# 2016_CARTE_PUISSANCE.net
KiCad netlist of a schematic drawn in Altium Designer
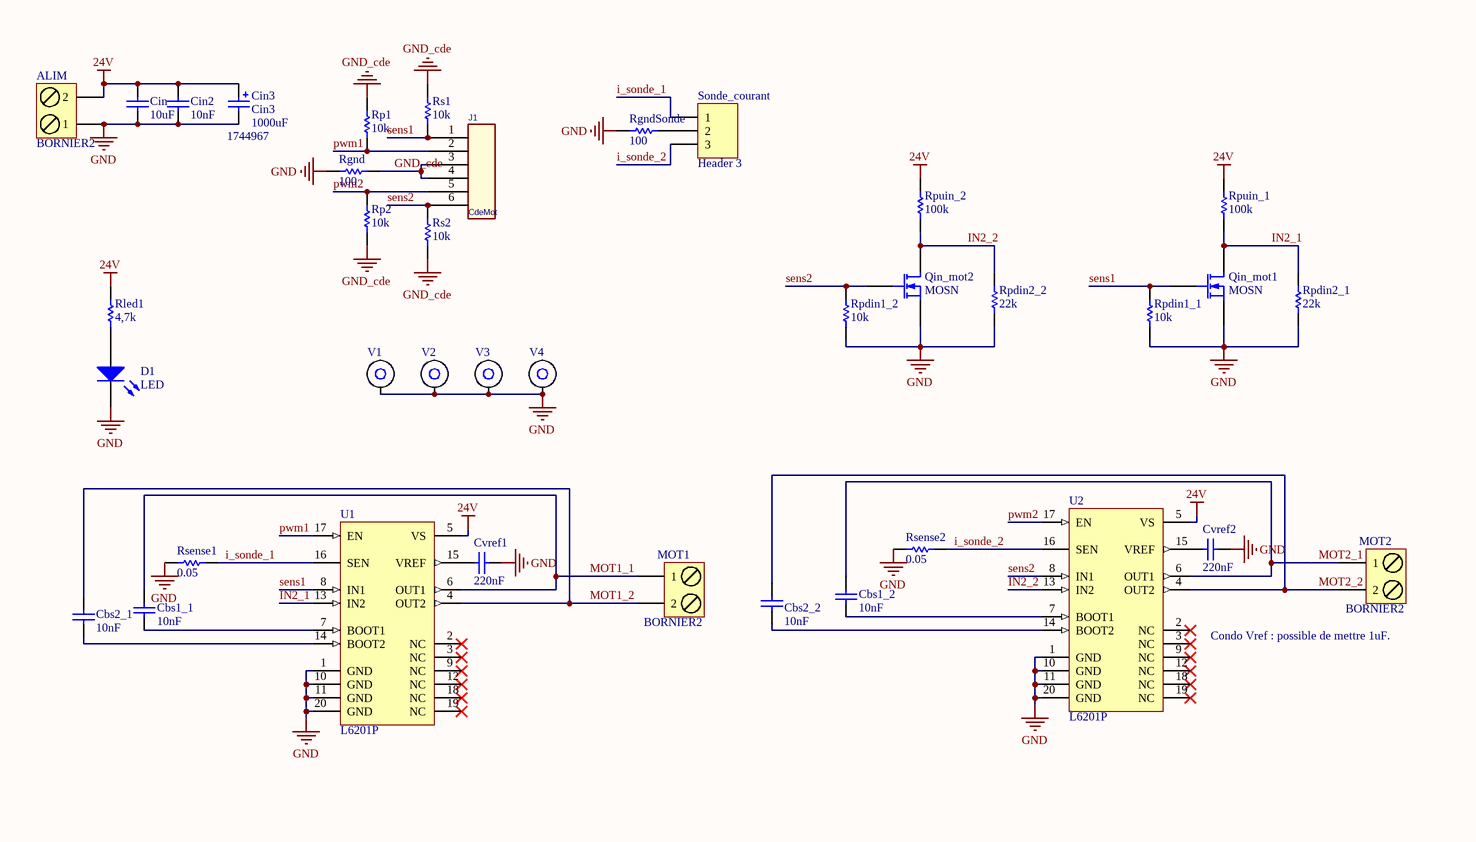
[diagram p0: 2016_CARTE_PUISSANCE.SchDoc, left]
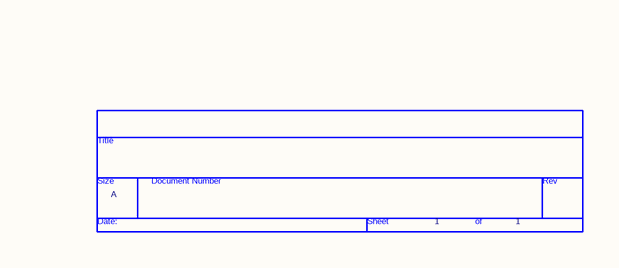
[diagram p1: 2016_CARTE_PUISSANCE.SchDoc, right]

(export (version "E")
  (design (tool "Eeschema 10.0.6"))
  (components
    (comp (ref "*")
      (value "TitleBlock0")
      (fields (field (name "PAGE COUNT") "1") (field (name "PAGE NUMBER") "1") (field (name "PAGE SIZE") "A"))
      (libsource (lib "*") (part "TitleBlock0"))
    )
    (comp (ref "ALIM")
      (value "BORNIER2")
      (footprint "BORNIER2")
      (description "Terminal blocks, 2 pins, pitch=5mm")
      (libsource (lib "Robot2010") (part "BORNIER2"))
    )
    (comp (ref "Cbs1_1")
      (value "10nF")
      (footprint "C0805_N")
      (description "Capacitor")
      (fields (field (name "PUBLISHER") "Altium Limited"))
      (libsource (lib "DG_Condensateur") (part "Capacitor"))
    )
    (comp (ref "Cbs1_2")
      (value "10nF")
      (footprint "C0805_N")
      (description "Capacitor")
      (fields (field (name "PUBLISHER") "Altium Limited"))
      (libsource (lib "DG_Condensateur") (part "Capacitor"))
    )
    (comp (ref "Cbs2_1")
      (value "10nF")
      (footprint "C0805_N")
      (description "Capacitor")
      (fields (field (name "PUBLISHER") "Altium Limited"))
      (libsource (lib "DG_Condensateur") (part "Capacitor"))
    )
    (comp (ref "Cbs2_2")
      (value "10nF")
      (footprint "C0805_N")
      (description "Capacitor")
      (fields (field (name "PUBLISHER") "Altium Limited"))
      (libsource (lib "DG_Condensateur") (part "Capacitor"))
    )
    (comp (ref "Cin")
      (value "10uF")
      (footprint "C1206_N")
      (description "Capacitor")
      (fields (field (name "PUBLISHER") "Altium Limited"))
      (libsource (lib "DG_Condensateur") (part "Capacitor"))
    )
    (comp (ref "Cin2")
      (value "10nF")
      (footprint "C0805_N")
      (description "Capacitor")
      (fields (field (name "PUBLISHER") "Altium Limited"))
      (libsource (lib "DG_Condensateur") (part "Capacitor"))
    )
    (comp (ref "Cin3")
      (value "Cin3")
      (footprint "COND_POL_RAD_5.08B")
      (description "Polarized Capacitor")
      (fields
        (field (name "ALTIUM_VALUE") "1000uF")
        (field (name "FAR") "1744967")
        (field (name "PUBLISHER") "Altium Limited")
      )
      (libsource (lib "Robot2010") (part "CONDENSATEUR_POLARISE"))
    )
    (comp (ref "Cvref1")
      (value "220nF")
      (footprint "C0805_N")
      (description "Capacitor")
      (fields (field (name "PUBLISHER") "Altium Limited"))
      (libsource (lib "DG_Condensateur") (part "Capacitor"))
    )
    (comp (ref "Cvref2")
      (value "220nF")
      (footprint "C0805_N")
      (description "Capacitor")
      (fields (field (name "PUBLISHER") "Altium Limited"))
      (libsource (lib "DG_Condensateur") (part "Capacitor"))
    )
    (comp (ref "D1")
      (value "LED")
      (footprint "LED_3mm")
      (description "Typical LED")
      (fields (field (name "PUBLISHER") "Altium Limited"))
      (libsource (lib "DG_LED") (part "LED"))
    )
    (comp (ref "J1") (value "CdeMot") (footprint "RJ11_6/6") (libsource (lib "*") (part "CONNECTEUR_RJ12")))
    (comp (ref "MOT1")
      (value "BORNIER2")
      (footprint "BORNIER2")
      (description "Terminal blocks, 2 pins, pitch=5mm")
      (libsource (lib "Connecteur") (part "BORNIER2"))
    )
    (comp (ref "MOT2")
      (value "BORNIER2")
      (footprint "BORNIER2")
      (description "Terminal blocks, 2 pins, pitch=5mm")
      (libsource (lib "Connecteur") (part "BORNIER2"))
    )
    (comp (ref "Qin_mot1")
      (value "MOSN")
      (footprint "SOT23-3N")
      (description "N-Channel MOSFET")
      (fields (field (name "PUBLISHER") "Altium Limited"))
      (libsource (lib "_ROBOT") (part "Transistor MOSFET-N"))
    )
    (comp (ref "Qin_mot2")
      (value "MOSN")
      (footprint "SOT23-3N")
      (description "N-Channel MOSFET")
      (fields (field (name "PUBLISHER") "Altium Limited"))
      (libsource (lib "_ROBOT") (part "Transistor MOSFET-N"))
    )
    (comp (ref "Rgnd")
      (value "100")
      (footprint "R1206_N")
      (description "Resistor")
      (fields (field (name "PUBLISHER") "Altium Limited"))
      (libsource (lib "DG_Resistance") (part "Resistor"))
    )
    (comp (ref "RgndSonde")
      (value "100")
      (footprint "R1206_N")
      (description "Resistor")
      (fields (field (name "PUBLISHER") "Altium Limited"))
      (libsource (lib "DG_Resistance") (part "Resistor"))
    )
    (comp (ref "Rled1")
      (value "4,7k")
      (footprint "R1206_N")
      (description "Resistor")
      (fields (field (name "PUBLISHER") "Altium Limited"))
      (libsource (lib "DG_Resistance") (part "Resistor"))
    )
    (comp (ref "Rp1")
      (value "10k")
      (footprint "R1206_N")
      (description "Resistor")
      (fields (field (name "PUBLISHER") "Altium Limited"))
      (libsource (lib "DG_Resistance") (part "Resistor"))
    )
    (comp (ref "Rp2")
      (value "10k")
      (footprint "R1206_N")
      (description "Resistor")
      (fields (field (name "PUBLISHER") "Altium Limited"))
      (libsource (lib "DG_Resistance") (part "Resistor"))
    )
    (comp (ref "Rpdin1_1")
      (value "10k")
      (footprint "R1206_N")
      (description "Resistor")
      (fields (field (name "PUBLISHER") "Altium Limited"))
      (libsource (lib "DG_Resistance") (part "Resistor"))
    )
    (comp (ref "Rpdin1_2")
      (value "10k")
      (footprint "R1206_N")
      (description "Resistor")
      (fields (field (name "PUBLISHER") "Altium Limited"))
      (libsource (lib "DG_Resistance") (part "Resistor"))
    )
    (comp (ref "Rpdin2_1")
      (value "22k")
      (footprint "R1206_N")
      (description "Resistor")
      (fields (field (name "PUBLISHER") "Altium Limited"))
      (libsource (lib "DG_Resistance") (part "Resistor"))
    )
    (comp (ref "Rpdin2_2")
      (value "22k")
      (footprint "R1206_N")
      (description "Resistor")
      (fields (field (name "PUBLISHER") "Altium Limited"))
      (libsource (lib "DG_Resistance") (part "Resistor"))
    )
    (comp (ref "Rpuin_1")
      (value "100k")
      (footprint "R1206_N")
      (description "Resistor")
      (fields (field (name "PUBLISHER") "Altium Limited"))
      (libsource (lib "DG_Resistance") (part "Resistor"))
    )
    (comp (ref "Rpuin_2")
      (value "100k")
      (footprint "R1206_N")
      (description "Resistor")
      (fields (field (name "PUBLISHER") "Altium Limited"))
      (libsource (lib "DG_Resistance") (part "Resistor"))
    )
    (comp (ref "Rs1")
      (value "10k")
      (footprint "R1206_N")
      (description "Resistor")
      (fields (field (name "PUBLISHER") "Altium Limited"))
      (libsource (lib "DG_Resistance") (part "Resistor"))
    )
    (comp (ref "Rs2")
      (value "10k")
      (footprint "R1206_N")
      (description "Resistor")
      (fields (field (name "PUBLISHER") "Altium Limited"))
      (libsource (lib "DG_Resistance") (part "Resistor"))
    )
    (comp (ref "Rsense1")
      (value "0.05")
      (footprint "R2512_N")
      (description "Resistor")
      (fields (field (name "PUBLISHER") "Altium Limited"))
      (libsource (lib "DG_Resistance") (part "Resistor"))
    )
    (comp (ref "Rsense2")
      (value "0.05")
      (footprint "R2512_N")
      (description "Resistor")
      (fields (field (name "PUBLISHER") "Altium Limited"))
      (libsource (lib "DG_Resistance") (part "Resistor"))
    )
    (comp (ref "Sonde_courant")
      (value "Header 3")
      (footprint "HDR1X3")
      (description "Header, 3-Pin")
      (fields (field (name "PUBLISHER") "Altium Limited"))
      (libsource (lib "DG_Connecteur") (part "Header 3"))
    )
    (comp (ref "U1")
      (value "L6201P")
      (footprint "PowerSO20_N")
      (description "DMOS Full Bridge Driver")
      (fields (field (name "PUBLISHER") "Altium Limited"))
      (libsource (lib "ST Interface DC Motor Controller") (part "L6201P"))
    )
    (comp (ref "U2")
      (value "L6201P")
      (footprint "PowerSO20_N")
      (description "DMOS Full Bridge Driver")
      (fields (field (name "PUBLISHER") "Altium Limited"))
      (libsource (lib "ST Interface DC Motor Controller") (part "L6201P"))
    )
    (comp (ref "V1")
      (value "Entretoise WURTH CMS")
      (footprint "ENTRETOISE_CMS")
      (description "Entretoise Wurth")
      (fields (field (name "PUBLISHER") "Damien Guitton"))
      (libsource (lib "_ROBOT") (part "Entretoise WURTH CMS"))
    )
    (comp (ref "V2")
      (value "Entretoise WURTH CMS")
      (footprint "ENTRETOISE_CMS")
      (description "Entretoise Wurth")
      (fields (field (name "PUBLISHER") "Damien Guitton"))
      (libsource (lib "_ROBOT") (part "Entretoise WURTH CMS"))
    )
    (comp (ref "V3")
      (value "Entretoise WURTH CMS")
      (footprint "ENTRETOISE_CMS")
      (description "Entretoise Wurth")
      (fields (field (name "PUBLISHER") "Damien Guitton"))
      (libsource (lib "_ROBOT") (part "Entretoise WURTH CMS"))
    )
    (comp (ref "V4")
      (value "Entretoise WURTH CMS")
      (footprint "ENTRETOISE_CMS")
      (description "Entretoise Wurth")
      (fields (field (name "PUBLISHER") "Damien Guitton"))
      (libsource (lib "_ROBOT") (part "Entretoise WURTH CMS"))
    )
  )
  (nets
    (net (code "1") (name "/IN2_1") (class "Default")
      (node (ref "Qin_mot1") (pin "3") (pinfunction "D_3") (pintype "passive"))
      (node (ref "Rpdin2_1") (pin "2") (pinfunction "2_2") (pintype "passive"))
      (node (ref "Rpuin_1") (pin "1") (pinfunction "1_1") (pintype "passive"))
      (node (ref "U1") (pin "13") (pinfunction "IN2_13") (pintype "input"))
    )
    (net (code "2") (name "/IN2_2") (class "Default")
      (node (ref "Qin_mot2") (pin "3") (pinfunction "D_3") (pintype "passive"))
      (node (ref "Rpdin2_2") (pin "2") (pinfunction "2_2") (pintype "passive"))
      (node (ref "Rpuin_2") (pin "1") (pinfunction "1_1") (pintype "passive"))
      (node (ref "U2") (pin "13") (pinfunction "IN2_13") (pintype "input"))
    )
    (net (code "3") (name "/MOT1_1") (class "Default")
      (node (ref "Cbs1_1") (pin "2") (pinfunction "2_2") (pintype "passive"))
      (node (ref "MOT1") (pin "1") (pinfunction "1_1") (pintype "passive"))
      (node (ref "U1") (pin "6") (pinfunction "OUT1_6") (pintype "output"))
    )
    (net (code "4") (name "/MOT1_2") (class "Default")
      (node (ref "Cbs2_1") (pin "2") (pinfunction "2_2") (pintype "passive"))
      (node (ref "MOT1") (pin "2") (pinfunction "2_2") (pintype "passive"))
      (node (ref "U1") (pin "4") (pinfunction "OUT2_4") (pintype "output"))
    )
    (net (code "5") (name "/MOT2_1") (class "Default")
      (node (ref "Cbs1_2") (pin "2") (pinfunction "2_2") (pintype "passive"))
      (node (ref "MOT2") (pin "1") (pinfunction "1_1") (pintype "passive"))
      (node (ref "U2") (pin "6") (pinfunction "OUT1_6") (pintype "output"))
    )
    (net (code "6") (name "/MOT2_2") (class "Default")
      (node (ref "Cbs2_2") (pin "2") (pinfunction "2_2") (pintype "passive"))
      (node (ref "MOT2") (pin "2") (pinfunction "2_2") (pintype "passive"))
      (node (ref "U2") (pin "4") (pinfunction "OUT2_4") (pintype "output"))
    )
    (net (code "7") (name "/i_sonde_1") (class "Default")
      (node (ref "Rsense1") (pin "2") (pinfunction "2_2") (pintype "passive"))
      (node (ref "Sonde_courant") (pin "1") (pinfunction "1_1") (pintype "passive"))
      (node (ref "U1") (pin "16") (pinfunction "SEN_16") (pintype "passive"))
    )
    (net (code "8") (name "/i_sonde_2") (class "Default")
      (node (ref "Rsense2") (pin "2") (pinfunction "2_2") (pintype "passive"))
      (node (ref "Sonde_courant") (pin "3") (pinfunction "3_3") (pintype "passive"))
      (node (ref "U2") (pin "16") (pinfunction "SEN_16") (pintype "passive"))
    )
    (net (code "9") (name "/pwm1") (class "Default")
      (node (ref "J1") (pin "2") (pinfunction "2_2") (pintype "passive"))
      (node (ref "Rp1") (pin "1") (pinfunction "1_1") (pintype "passive"))
      (node (ref "U1") (pin "17") (pinfunction "EN_17") (pintype "input"))
    )
    (net (code "10") (name "/pwm2") (class "Default")
      (node (ref "J1") (pin "5") (pinfunction "5_5") (pintype "passive"))
      (node (ref "Rp2") (pin "2") (pinfunction "2_2") (pintype "passive"))
      (node (ref "U2") (pin "17") (pinfunction "EN_17") (pintype "input"))
    )
    (net (code "11") (name "/sens1") (class "Default")
      (node (ref "J1") (pin "1") (pinfunction "1_1") (pintype "passive"))
      (node (ref "Qin_mot1") (pin "1") (pinfunction "G_1") (pintype "passive"))
      (node (ref "Rpdin1_1") (pin "1") (pinfunction "1_1") (pintype "passive"))
      (node (ref "Rs1") (pin "1") (pinfunction "1_1") (pintype "passive"))
      (node (ref "U1") (pin "8") (pinfunction "IN1_8") (pintype "input"))
    )
    (net (code "12") (name "/sens2") (class "Default")
      (node (ref "J1") (pin "6") (pinfunction "6_6") (pintype "passive"))
      (node (ref "Qin_mot2") (pin "1") (pinfunction "G_1") (pintype "passive"))
      (node (ref "Rpdin1_2") (pin "1") (pinfunction "1_1") (pintype "passive"))
      (node (ref "Rs2") (pin "2") (pinfunction "2_2") (pintype "passive"))
      (node (ref "U2") (pin "8") (pinfunction "IN1_8") (pintype "input"))
    )
    (net (code "13") (name "24V") (class "Default")
      (node (ref "ALIM") (pin "2") (pinfunction "2_2") (pintype "passive"))
      (node (ref "Cin") (pin "2") (pinfunction "2_2") (pintype "passive"))
      (node (ref "Cin2") (pin "2") (pinfunction "2_2") (pintype "passive"))
      (node (ref "Cin3") (pin "1") (pinfunction "1_1") (pintype "passive"))
      (node (ref "Rled1") (pin "2") (pinfunction "2_2") (pintype "passive"))
      (node (ref "Rpuin_1") (pin "2") (pinfunction "2_2") (pintype "passive"))
      (node (ref "Rpuin_2") (pin "2") (pinfunction "2_2") (pintype "passive"))
      (node (ref "U1") (pin "5") (pinfunction "VS_5") (pintype "power_in"))
      (node (ref "U2") (pin "5") (pinfunction "VS_5") (pintype "power_in"))
    )
    (net (code "14") (name "GND") (class "Default")
      (node (ref "ALIM") (pin "1") (pinfunction "1_1") (pintype "passive"))
      (node (ref "Cin") (pin "1") (pinfunction "1_1") (pintype "passive"))
      (node (ref "Cin2") (pin "1") (pinfunction "1_1") (pintype "passive"))
      (node (ref "Cin3") (pin "2") (pinfunction "2_2") (pintype "passive"))
      (node (ref "Cvref1") (pin "1") (pinfunction "1_1") (pintype "passive"))
      (node (ref "Cvref2") (pin "1") (pinfunction "1_1") (pintype "passive"))
      (node (ref "D1") (pin "2") (pinfunction "2_2") (pintype "passive"))
      (node (ref "Qin_mot1") (pin "2") (pinfunction "S_2") (pintype "passive"))
      (node (ref "Qin_mot2") (pin "2") (pinfunction "S_2") (pintype "passive"))
      (node (ref "Rgnd") (pin "2") (pinfunction "2_2") (pintype "passive"))
      (node (ref "RgndSonde") (pin "2") (pinfunction "2_2") (pintype "passive"))
      (node (ref "Rpdin1_1") (pin "2") (pinfunction "2_2") (pintype "passive"))
      (node (ref "Rpdin1_2") (pin "2") (pinfunction "2_2") (pintype "passive"))
      (node (ref "Rpdin2_1") (pin "1") (pinfunction "1_1") (pintype "passive"))
      (node (ref "Rpdin2_2") (pin "1") (pinfunction "1_1") (pintype "passive"))
      (node (ref "Rsense1") (pin "1") (pinfunction "1_1") (pintype "passive"))
      (node (ref "Rsense2") (pin "1") (pinfunction "1_1") (pintype "passive"))
      (node (ref "U1") (pin "1") (pinfunction "GND_1") (pintype "power_in"))
      (node (ref "U1") (pin "10") (pinfunction "GND_10") (pintype "power_in"))
      (node (ref "U1") (pin "11") (pinfunction "GND_11") (pintype "power_in"))
      (node (ref "U1") (pin "20") (pinfunction "GND_20") (pintype "power_in"))
      (node (ref "U2") (pin "1") (pinfunction "GND_1") (pintype "power_in"))
      (node (ref "U2") (pin "10") (pinfunction "GND_10") (pintype "power_in"))
      (node (ref "U2") (pin "11") (pinfunction "GND_11") (pintype "power_in"))
      (node (ref "U2") (pin "20") (pinfunction "GND_20") (pintype "power_in"))
      (node (ref "V1") (pin "1") (pinfunction "1_1") (pintype "passive"))
      (node (ref "V2") (pin "1") (pinfunction "1_1") (pintype "passive"))
      (node (ref "V3") (pin "1") (pinfunction "1_1") (pintype "passive"))
      (node (ref "V4") (pin "1") (pinfunction "1_1") (pintype "passive"))
    )
    (net (code "15") (name "GND_cde") (class "Default")
      (node (ref "J1") (pin "3") (pinfunction "3_3") (pintype "passive"))
      (node (ref "J1") (pin "4") (pinfunction "4_4") (pintype "passive"))
      (node (ref "Rgnd") (pin "1") (pinfunction "1_1") (pintype "passive"))
      (node (ref "Rp1") (pin "2") (pinfunction "2_2") (pintype "passive"))
      (node (ref "Rp2") (pin "1") (pinfunction "1_1") (pintype "passive"))
      (node (ref "Rs1") (pin "2") (pinfunction "2_2") (pintype "passive"))
      (node (ref "Rs2") (pin "1") (pinfunction "1_1") (pintype "passive"))
    )
    (net (code "16") (name "Net-(D1-Pad1)") (class "Default")
      (node (ref "D1") (pin "1") (pinfunction "1_1") (pintype "passive"))
      (node (ref "Rled1") (pin "1") (pinfunction "1_1") (pintype "passive"))
    )
    (net (code "17") (name "Net-(RgndSonde-Pad1)") (class "Default")
      (node (ref "RgndSonde") (pin "1") (pinfunction "1_1") (pintype "passive"))
      (node (ref "Sonde_courant") (pin "2") (pinfunction "2_2") (pintype "passive"))
    )
    (net (code "18") (name "Net-(U1-BOOT1)") (class "Default")
      (node (ref "Cbs1_1") (pin "1") (pinfunction "1_1") (pintype "passive"))
      (node (ref "U1") (pin "7") (pinfunction "BOOT1_7") (pintype "input"))
    )
    (net (code "19") (name "Net-(U1-BOOT2)") (class "Default")
      (node (ref "Cbs2_1") (pin "1") (pinfunction "1_1") (pintype "passive"))
      (node (ref "U1") (pin "14") (pinfunction "BOOT2_14") (pintype "input"))
    )
    (net (code "20") (name "Net-(U1-VREF)") (class "Default")
      (node (ref "Cvref1") (pin "2") (pinfunction "2_2") (pintype "passive"))
      (node (ref "U1") (pin "15") (pinfunction "VREF_15") (pintype "output"))
    )
    (net (code "21") (name "Net-(U2-BOOT1)") (class "Default")
      (node (ref "Cbs1_2") (pin "1") (pinfunction "1_1") (pintype "passive"))
      (node (ref "U2") (pin "7") (pinfunction "BOOT1_7") (pintype "input"))
    )
    (net (code "22") (name "Net-(U2-BOOT2)") (class "Default")
      (node (ref "Cbs2_2") (pin "1") (pinfunction "1_1") (pintype "passive"))
      (node (ref "U2") (pin "14") (pinfunction "BOOT2_14") (pintype "input"))
    )
    (net (code "23") (name "Net-(U2-VREF)") (class "Default")
      (node (ref "Cvref2") (pin "2") (pinfunction "2_2") (pintype "passive"))
      (node (ref "U2") (pin "15") (pinfunction "VREF_15") (pintype "output"))
    )
    (net (code "24") (name "unconnected-(U1-NC-Pad2)") (class "Default")
      (node (ref "U1") (pin "2") (pinfunction "NC_2") (pintype "passive+no_connect"))
    )
    (net (code "25") (name "unconnected-(U1-NC-Pad3)") (class "Default")
      (node (ref "U1") (pin "3") (pinfunction "NC_3") (pintype "passive+no_connect"))
    )
    (net (code "26") (name "unconnected-(U1-NC-Pad9)") (class "Default")
      (node (ref "U1") (pin "9") (pinfunction "NC_9") (pintype "passive+no_connect"))
    )
    (net (code "27") (name "unconnected-(U1-NC-Pad12)") (class "Default")
      (node (ref "U1") (pin "12") (pinfunction "NC_12") (pintype "passive+no_connect"))
    )
    (net (code "28") (name "unconnected-(U1-NC-Pad18)") (class "Default")
      (node (ref "U1") (pin "18") (pinfunction "NC_18") (pintype "passive+no_connect"))
    )
    (net (code "29") (name "unconnected-(U1-NC-Pad19)") (class "Default")
      (node (ref "U1") (pin "19") (pinfunction "NC_19") (pintype "passive+no_connect"))
    )
    (net (code "30") (name "unconnected-(U2-NC-Pad2)") (class "Default")
      (node (ref "U2") (pin "2") (pinfunction "NC_2") (pintype "passive+no_connect"))
    )
    (net (code "31") (name "unconnected-(U2-NC-Pad3)") (class "Default")
      (node (ref "U2") (pin "3") (pinfunction "NC_3") (pintype "passive+no_connect"))
    )
    (net (code "32") (name "unconnected-(U2-NC-Pad9)") (class "Default")
      (node (ref "U2") (pin "9") (pinfunction "NC_9") (pintype "passive+no_connect"))
    )
    (net (code "33") (name "unconnected-(U2-NC-Pad12)") (class "Default")
      (node (ref "U2") (pin "12") (pinfunction "NC_12") (pintype "passive+no_connect"))
    )
    (net (code "34") (name "unconnected-(U2-NC-Pad18)") (class "Default")
      (node (ref "U2") (pin "18") (pinfunction "NC_18") (pintype "passive+no_connect"))
    )
    (net (code "35") (name "unconnected-(U2-NC-Pad19)") (class "Default")
      (node (ref "U2") (pin "19") (pinfunction "NC_19") (pintype "passive+no_connect"))
    )
  )
)
